# USBC.net
KiCad netlist of a schematic drawn in Altium Designer
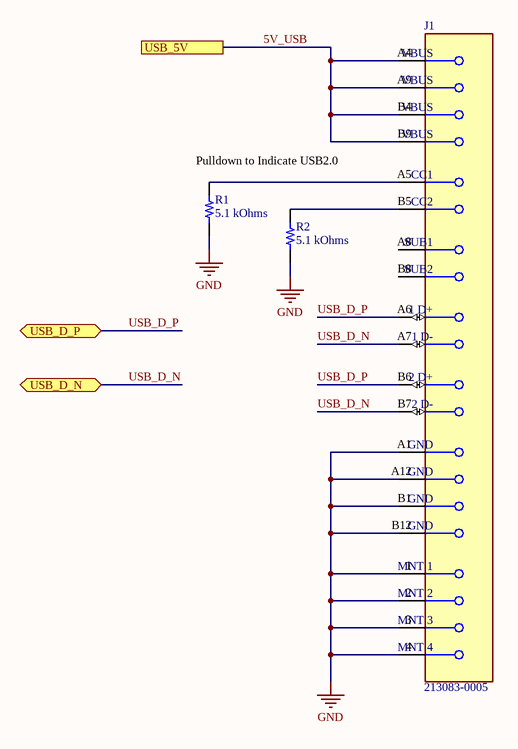
[diagram p0: USBC.SchDoc]

(export (version "E")
  (design (tool "Eeschema 10.0.6"))
  (components
    (comp (ref "J1")
      (value "213083-0005")
      (footprint "FP-2130830005-MFG")
      (description "CONN RCP USB2.0 TYP C 24P SMD RA")
      (libsource (lib "Altium Content Vault") (part "19c02d2f2bfb43c17c60460c929b15b"))
    )
    (comp (ref "R1")
      (value "5.1 kOhms")
      (footprint "RES 0603_1608")
      (description "RES 5.1K OHM 0.1% 1/10W 0603")
      (fields (field (name "PART NUMBER") "TNPW06035K10BYEN") (field (name "MANUFACTURER") "Vishay Dale"))
      (libsource (lib "Celestial Altium Library - altium_library") (part "Resistor"))
    )
    (comp (ref "R2")
      (value "5.1 kOhms")
      (footprint "RES 0603_1608")
      (description "RES 5.1K OHM 0.1% 1/10W 0603")
      (fields (field (name "PART NUMBER") "TNPW06035K10BYEN") (field (name "MANUFACTURER") "Vishay Dale"))
      (libsource (lib "Celestial Altium Library - altium_library") (part "Resistor"))
    )
  )
  (nets
    (net (code "1") (name "/5V_USB") (class "Default")
      (node (ref "J1") (pin "A4") (pinfunction "VBUS_A4") (pintype "power_in"))
      (node (ref "J1") (pin "A9") (pinfunction "VBUS_A9") (pintype "power_in"))
      (node (ref "J1") (pin "B4") (pinfunction "VBUS_B4") (pintype "power_in"))
      (node (ref "J1") (pin "B9") (pinfunction "VBUS_B9") (pintype "power_in"))
    )
    (net (code "2") (name "/USB_D_N") (class "Default")
      (node (ref "J1") (pin "A7") (pinfunction "1_D-_A7") (pintype "bidirectional"))
      (node (ref "J1") (pin "B7") (pinfunction "2_D-_B7") (pintype "bidirectional"))
    )
    (net (code "3") (name "/USB_D_P") (class "Default")
      (node (ref "J1") (pin "A6") (pinfunction "1_D+_A6") (pintype "bidirectional"))
      (node (ref "J1") (pin "B6") (pinfunction "2_D+_B6") (pintype "bidirectional"))
    )
    (net (code "4") (name "GND") (class "Default")
      (node (ref "J1") (pin "1") (pinfunction "MNT_1_1") (pintype "passive"))
      (node (ref "J1") (pin "2") (pinfunction "MNT_2_2") (pintype "passive"))
      (node (ref "J1") (pin "3") (pinfunction "MNT_3_3") (pintype "passive"))
      (node (ref "J1") (pin "4") (pinfunction "MNT_4_4") (pintype "passive"))
      (node (ref "J1") (pin "A1") (pinfunction "GND_A1") (pintype "power_in"))
      (node (ref "J1") (pin "A12") (pinfunction "GND_A12") (pintype "power_in"))
      (node (ref "J1") (pin "B1") (pinfunction "GND_B1") (pintype "power_in"))
      (node (ref "J1") (pin "B12") (pinfunction "GND_B12") (pintype "power_in"))
      (node (ref "R1") (pin "1") (pinfunction "1_1") (pintype "passive"))
      (node (ref "R2") (pin "1") (pinfunction "1_1") (pintype "passive"))
    )
    (net (code "5") (name "Net-(J1-CC1)") (class "Default")
      (node (ref "J1") (pin "A5") (pinfunction "CC1_A5") (pintype "passive"))
      (node (ref "R1") (pin "2") (pinfunction "2_2") (pintype "passive"))
    )
    (net (code "6") (name "Net-(J1-CC2)") (class "Default")
      (node (ref "J1") (pin "B5") (pinfunction "CC2_B5") (pintype "passive"))
      (node (ref "R2") (pin "2") (pinfunction "2_2") (pintype "passive"))
    )
    (net (code "7") (name "unconnected-(J1-SUB1-PadA8)") (class "Default")
      (node (ref "J1") (pin "A8") (pinfunction "SUB1_A8") (pintype "passive"))
    )
    (net (code "8") (name "unconnected-(J1-SUB2-PadB8)") (class "Default")
      (node (ref "J1") (pin "B8") (pinfunction "SUB2_B8") (pintype "passive"))
    )
  )
)
